# ONET8501P-breakout.net
KiCad netlist of a schematic drawn in EAGLE
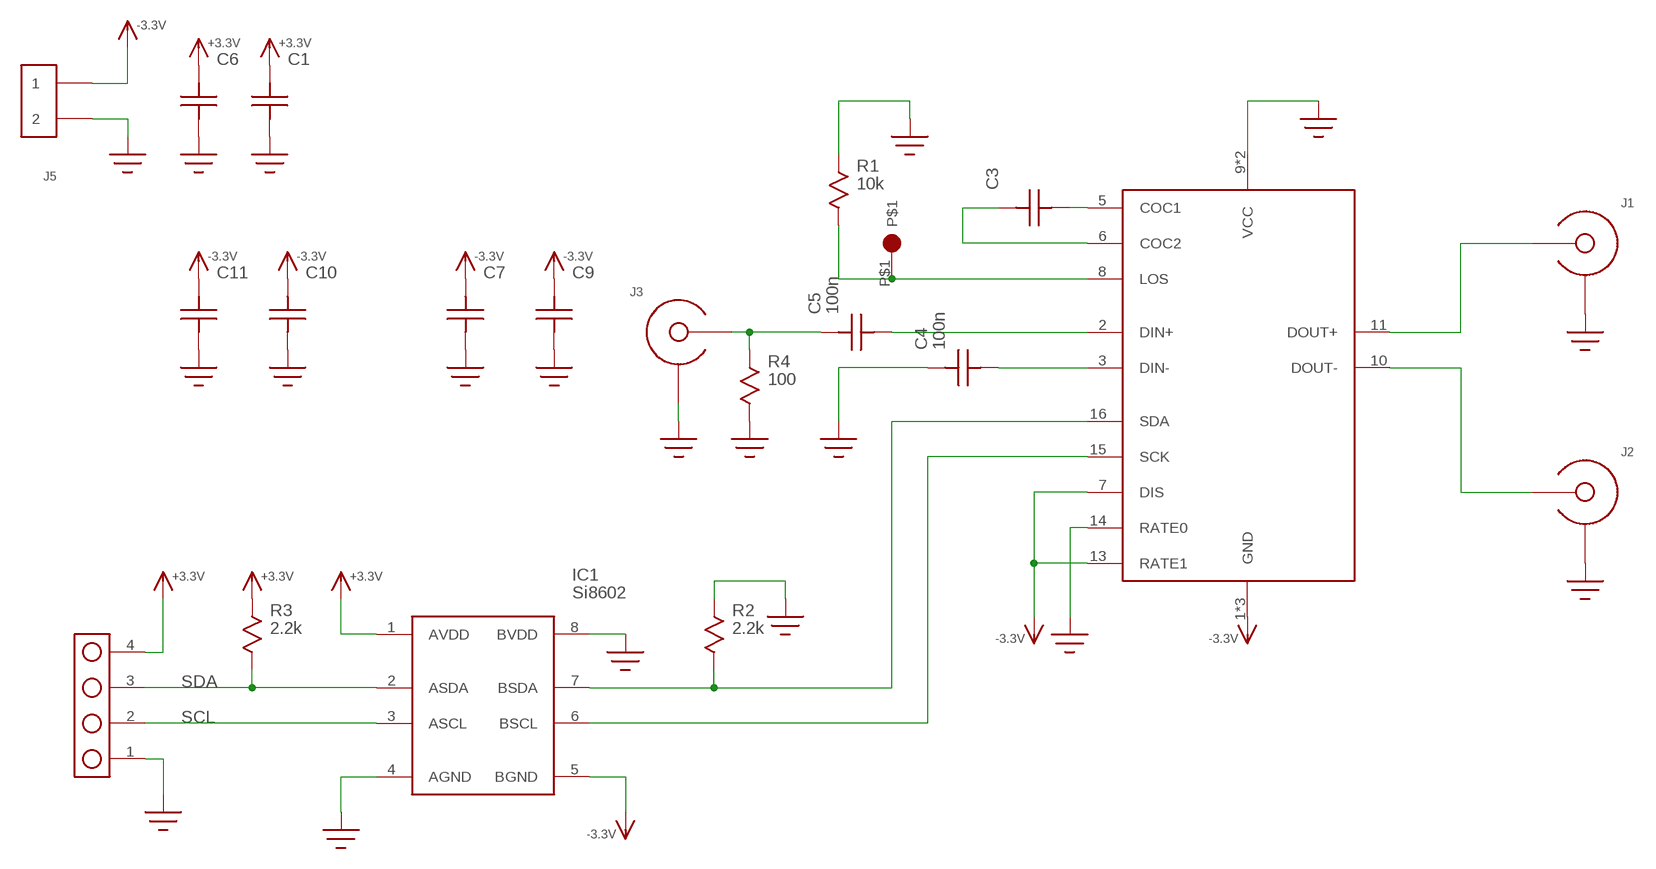
[diagram p0: schematic, sheet 1]

(export (version "E")
  (design (tool "Eeschema 10.0.6"))
  (components
    (comp (ref "C1")
      (value "C0603")
      (footprint "eagle-import:C0603")
      (libsource (lib "eagle-import") (part "C0603"))
    )
    (comp (ref "C3")
      (value "C0603")
      (footprint "eagle-import:C0603")
      (libsource (lib "eagle-import") (part "C0603"))
    )
    (comp (ref "C4")
      (value "100n")
      (footprint "eagle-import:C0603")
      (libsource (lib "eagle-import") (part "C0603"))
    )
    (comp (ref "C5")
      (value "100n")
      (footprint "eagle-import:C0603")
      (libsource (lib "eagle-import") (part "C0603"))
    )
    (comp (ref "C6")
      (value "C1206")
      (footprint "eagle-import:1206")
      (libsource (lib "eagle-import") (part "C1206"))
    )
    (comp (ref "C7")
      (value "C1206")
      (footprint "eagle-import:1206")
      (libsource (lib "eagle-import") (part "C1206"))
    )
    (comp (ref "C9")
      (value "C0603")
      (footprint "eagle-import:C0603")
      (libsource (lib "eagle-import") (part "C0603"))
    )
    (comp (ref "C10")
      (value "C0603")
      (footprint "eagle-import:C0603")
      (libsource (lib "eagle-import") (part "C0603"))
    )
    (comp (ref "C11")
      (value "C0603")
      (footprint "eagle-import:C0603")
      (libsource (lib "eagle-import") (part "C0603"))
    )
    (comp (ref "IC1")
      (value "Si8602")
      (footprint "eagle-import:SOIC8")
      (libsource (lib "eagle-import") (part "SI8602"))
    )
    (comp (ref "IC2")
      (value "ONET8501P")
      (footprint "eagle-import:TQFN16-EP")
      (libsource (lib "eagle-import") (part "ONET8501P"))
    )
    (comp (ref "J1")
      (value "SMA-EDGE-LAUNCH4L_4035_TAPER")
      (footprint "eagle-import:SMA_EDGE_LAUNCH_4L_4035_TAPER")
      (libsource (lib "eagle-import") (part "SMA-EDGE-LAUNCH4L_4035_TAPER"))
    )
    (comp (ref "J2")
      (value "SMA-EDGE-LAUNCH4L_4035_TAPER")
      (footprint "eagle-import:SMA_EDGE_LAUNCH_4L_4035_TAPER")
      (libsource (lib "eagle-import") (part "SMA-EDGE-LAUNCH4L_4035_TAPER"))
    )
    (comp (ref "J3")
      (value "SMA-EDGE-LAUNCH4L_4035_TAPER")
      (footprint "eagle-import:SMA_EDGE_LAUNCH_4L_4035_TAPER")
      (libsource (lib "eagle-import") (part "SMA-EDGE-LAUNCH4L_4035_TAPER"))
    )
    (comp (ref "J4")
      (value "HEADER_4PIN")
      (footprint "eagle-import:HEADER_4PIN")
      (libsource (lib "eagle-import") (part "HEADER_4PIN"))
    )
    (comp (ref "J5")
      (value "HEADER_2PIN")
      (footprint "eagle-import:HEADER_2PIN")
      (libsource (lib "eagle-import") (part "HEADER_2PIN"))
    )
    (comp (ref "P1")
      (value "ICSP_PAD")
      (footprint "eagle-import:ICSP_PAD")
      (libsource (lib "eagle-import") (part "ICSP_PAD"))
    )
    (comp (ref "R1")
      (value "10k")
      (footprint "eagle-import:R0603")
      (libsource (lib "eagle-import") (part "R0603"))
    )
    (comp (ref "R2")
      (value "2.2k")
      (footprint "eagle-import:R0603")
      (libsource (lib "eagle-import") (part "R0603"))
    )
    (comp (ref "R3")
      (value "2.2k")
      (footprint "eagle-import:R0603")
      (libsource (lib "eagle-import") (part "R0603"))
    )
    (comp (ref "R4")
      (value "100")
      (footprint "eagle-import:R0603")
      (libsource (lib "eagle-import") (part "R0603"))
    )
  )
  (nets
    (net (code "1") (name "+3.3V") (class "Default")
      (node (ref "C1") (pin "P$2") (pinfunction "P$2_P$2") (pintype "bidirectional"))
      (node (ref "C6") (pin "P$2") (pinfunction "P$2_P$2") (pintype "bidirectional"))
      (node (ref "IC1") (pin "1") (pinfunction "AVDD_1") (pintype "bidirectional"))
      (node (ref "J4") (pin "4") (pinfunction "4_4") (pintype "bidirectional"))
      (node (ref "R3") (pin "P$1") (pinfunction "P$3_P$1") (pintype "bidirectional"))
    )
    (net (code "2") (name "-3.3V") (class "Default")
      (node (ref "C10") (pin "P$2") (pinfunction "P$2_P$2") (pintype "bidirectional"))
      (node (ref "C11") (pin "P$2") (pinfunction "P$2_P$2") (pintype "bidirectional"))
      (node (ref "C7") (pin "P$2") (pinfunction "P$2_P$2") (pintype "bidirectional"))
      (node (ref "C9") (pin "P$2") (pinfunction "P$2_P$2") (pintype "bidirectional"))
      (node (ref "IC1") (pin "5") (pinfunction "BGND_5") (pintype "bidirectional"))
      (node (ref "IC2") (pin "1") (pinfunction "GND_1") (pintype "bidirectional"))
      (node (ref "IC2") (pin "13") (pinfunction "RATE1_13") (pintype "bidirectional"))
      (node (ref "IC2") (pin "4") (pinfunction "GND_4") (pintype "bidirectional"))
      (node (ref "IC2") (pin "7") (pinfunction "DIS_7") (pintype "bidirectional"))
      (node (ref "IC2") (pin "EP") (pinfunction "GND_EP") (pintype "bidirectional"))
      (node (ref "J5") (pin "1") (pinfunction "1_1") (pintype "bidirectional"))
    )
    (net (code "3") (name "/SCL") (class "Default")
      (node (ref "IC1") (pin "3") (pinfunction "ASCL_3") (pintype "bidirectional"))
      (node (ref "J4") (pin "2") (pinfunction "2_2") (pintype "bidirectional"))
    )
    (net (code "4") (name "/SDA") (class "Default")
      (node (ref "IC1") (pin "2") (pinfunction "ASDA_2") (pintype "bidirectional"))
      (node (ref "J4") (pin "3") (pinfunction "3_3") (pintype "bidirectional"))
      (node (ref "R3") (pin "P$2") (pinfunction "P$4_P$2") (pintype "bidirectional"))
    )
    (net (code "5") (name "GND") (class "Default")
      (node (ref "C1") (pin "P$1") (pinfunction "P$1_P$1") (pintype "bidirectional"))
      (node (ref "C10") (pin "P$1") (pinfunction "P$1_P$1") (pintype "bidirectional"))
      (node (ref "C11") (pin "P$1") (pinfunction "P$1_P$1") (pintype "bidirectional"))
      (node (ref "C4") (pin "P$2") (pinfunction "P$2_P$2") (pintype "bidirectional"))
      (node (ref "C6") (pin "P$1") (pinfunction "P$1_P$1") (pintype "bidirectional"))
      (node (ref "C7") (pin "P$1") (pinfunction "P$1_P$1") (pintype "bidirectional"))
      (node (ref "C9") (pin "P$1") (pinfunction "P$1_P$1") (pintype "bidirectional"))
      (node (ref "IC1") (pin "4") (pinfunction "AGND_4") (pintype "bidirectional"))
      (node (ref "IC1") (pin "8") (pinfunction "BVDD_8") (pintype "bidirectional"))
      (node (ref "IC2") (pin "12") (pinfunction "VCC_12") (pintype "bidirectional"))
      (node (ref "IC2") (pin "14") (pinfunction "RATE0_14") (pintype "bidirectional"))
      (node (ref "IC2") (pin "9") (pinfunction "VCC_9") (pintype "bidirectional"))
      (node (ref "J1") (pin "BOTTOM_GND") (pinfunction "SHIELD_BOTTOM_GND") (pintype "bidirectional"))
      (node (ref "J1") (pin "GND@1") (pinfunction "SHIELD_GND@1") (pintype "bidirectional"))
      (node (ref "J1") (pin "GND@14") (pinfunction "SHIELD_GND@14") (pintype "bidirectional"))
      (node (ref "J1") (pin "GND@15") (pinfunction "SHIELD_GND@15") (pintype "bidirectional"))
      (node (ref "J1") (pin "GND@16") (pinfunction "SHIELD_GND@16") (pintype "bidirectional"))
      (node (ref "J1") (pin "GND@17") (pinfunction "SHIELD_GND@17") (pintype "bidirectional"))
      (node (ref "J1") (pin "GND@2") (pinfunction "SHIELD_GND@2") (pintype "bidirectional"))
      (node (ref "J1") (pin "GND@3") (pinfunction "SHIELD_GND@3") (pintype "bidirectional"))
      (node (ref "J1") (pin "GND@4") (pinfunction "SHIELD_GND@4") (pintype "bidirectional"))
      (node (ref "J1") (pin "GND@5") (pinfunction "SHIELD_GND@5") (pintype "bidirectional"))
      (node (ref "J1") (pin "GND@6") (pinfunction "SHIELD_GND@6") (pintype "bidirectional"))
      (node (ref "J1") (pin "GND@7") (pinfunction "SHIELD_GND@7") (pintype "bidirectional"))
      (node (ref "J1") (pin "GND@8") (pinfunction "SHIELD_GND@8") (pintype "bidirectional"))
      (node (ref "J1") (pin "GND_PAD1") (pinfunction "SHIELD_GND_PAD1") (pintype "bidirectional"))
      (node (ref "J1") (pin "GND_PAD2") (pinfunction "SHIELD_GND_PAD2") (pintype "bidirectional"))
      (node (ref "J1") (pin "P$1") (pinfunction "SHIELD_P$1") (pintype "bidirectional"))
      (node (ref "J1") (pin "P$2") (pinfunction "SHIELD_P$2") (pintype "bidirectional"))
      (node (ref "J2") (pin "BOTTOM_GND") (pinfunction "SHIELD_BOTTOM_GND") (pintype "bidirectional"))
      (node (ref "J2") (pin "GND@1") (pinfunction "SHIELD_GND@1") (pintype "bidirectional"))
      (node (ref "J2") (pin "GND@14") (pinfunction "SHIELD_GND@14") (pintype "bidirectional"))
      (node (ref "J2") (pin "GND@15") (pinfunction "SHIELD_GND@15") (pintype "bidirectional"))
      (node (ref "J2") (pin "GND@16") (pinfunction "SHIELD_GND@16") (pintype "bidirectional"))
      (node (ref "J2") (pin "GND@17") (pinfunction "SHIELD_GND@17") (pintype "bidirectional"))
      (node (ref "J2") (pin "GND@2") (pinfunction "SHIELD_GND@2") (pintype "bidirectional"))
      (node (ref "J2") (pin "GND@3") (pinfunction "SHIELD_GND@3") (pintype "bidirectional"))
      (node (ref "J2") (pin "GND@4") (pinfunction "SHIELD_GND@4") (pintype "bidirectional"))
      (node (ref "J2") (pin "GND@5") (pinfunction "SHIELD_GND@5") (pintype "bidirectional"))
      (node (ref "J2") (pin "GND@6") (pinfunction "SHIELD_GND@6") (pintype "bidirectional"))
      (node (ref "J2") (pin "GND@7") (pinfunction "SHIELD_GND@7") (pintype "bidirectional"))
      (node (ref "J2") (pin "GND@8") (pinfunction "SHIELD_GND@8") (pintype "bidirectional"))
      (node (ref "J2") (pin "GND_PAD1") (pinfunction "SHIELD_GND_PAD1") (pintype "bidirectional"))
      (node (ref "J2") (pin "GND_PAD2") (pinfunction "SHIELD_GND_PAD2") (pintype "bidirectional"))
      (node (ref "J2") (pin "P$1") (pinfunction "SHIELD_P$1") (pintype "bidirectional"))
      (node (ref "J2") (pin "P$2") (pinfunction "SHIELD_P$2") (pintype "bidirectional"))
      (node (ref "J3") (pin "BOTTOM_GND") (pinfunction "SHIELD_BOTTOM_GND") (pintype "bidirectional"))
      (node (ref "J3") (pin "GND@1") (pinfunction "SHIELD_GND@1") (pintype "bidirectional"))
      (node (ref "J3") (pin "GND@14") (pinfunction "SHIELD_GND@14") (pintype "bidirectional"))
      (node (ref "J3") (pin "GND@15") (pinfunction "SHIELD_GND@15") (pintype "bidirectional"))
      (node (ref "J3") (pin "GND@16") (pinfunction "SHIELD_GND@16") (pintype "bidirectional"))
      (node (ref "J3") (pin "GND@17") (pinfunction "SHIELD_GND@17") (pintype "bidirectional"))
      (node (ref "J3") (pin "GND@2") (pinfunction "SHIELD_GND@2") (pintype "bidirectional"))
      (node (ref "J3") (pin "GND@3") (pinfunction "SHIELD_GND@3") (pintype "bidirectional"))
      (node (ref "J3") (pin "GND@4") (pinfunction "SHIELD_GND@4") (pintype "bidirectional"))
      (node (ref "J3") (pin "GND@5") (pinfunction "SHIELD_GND@5") (pintype "bidirectional"))
      (node (ref "J3") (pin "GND@6") (pinfunction "SHIELD_GND@6") (pintype "bidirectional"))
      (node (ref "J3") (pin "GND@7") (pinfunction "SHIELD_GND@7") (pintype "bidirectional"))
      (node (ref "J3") (pin "GND@8") (pinfunction "SHIELD_GND@8") (pintype "bidirectional"))
      (node (ref "J3") (pin "GND_PAD1") (pinfunction "SHIELD_GND_PAD1") (pintype "bidirectional"))
      (node (ref "J3") (pin "GND_PAD2") (pinfunction "SHIELD_GND_PAD2") (pintype "bidirectional"))
      (node (ref "J3") (pin "P$1") (pinfunction "SHIELD_P$1") (pintype "bidirectional"))
      (node (ref "J3") (pin "P$2") (pinfunction "SHIELD_P$2") (pintype "bidirectional"))
      (node (ref "J4") (pin "1") (pinfunction "1_1") (pintype "bidirectional"))
      (node (ref "J5") (pin "2") (pinfunction "2_2") (pintype "bidirectional"))
      (node (ref "R1") (pin "P$1") (pinfunction "P$3_P$1") (pintype "bidirectional"))
      (node (ref "R2") (pin "P$1") (pinfunction "P$3_P$1") (pintype "bidirectional"))
      (node (ref "R4") (pin "P$2") (pinfunction "P$4_P$2") (pintype "bidirectional"))
    )
    (net (code "6") (name "Net-(IC1-BSCL)") (class "Default")
      (node (ref "IC1") (pin "6") (pinfunction "BSCL_6") (pintype "bidirectional"))
      (node (ref "IC2") (pin "15") (pinfunction "SCK_15") (pintype "bidirectional"))
    )
    (net (code "7") (name "Net-(IC1-BSDA)") (class "Default")
      (node (ref "IC1") (pin "7") (pinfunction "BSDA_7") (pintype "bidirectional"))
      (node (ref "IC2") (pin "16") (pinfunction "SDA_16") (pintype "bidirectional"))
      (node (ref "R2") (pin "P$2") (pinfunction "P$4_P$2") (pintype "bidirectional"))
    )
    (net (code "8") (name "Net-(IC2-COC1)") (class "Default")
      (node (ref "C3") (pin "P$1") (pinfunction "P$1_P$1") (pintype "bidirectional"))
      (node (ref "IC2") (pin "5") (pinfunction "COC1_5") (pintype "bidirectional"))
    )
    (net (code "9") (name "Net-(IC2-COC2)") (class "Default")
      (node (ref "C3") (pin "P$2") (pinfunction "P$2_P$2") (pintype "bidirectional"))
      (node (ref "IC2") (pin "6") (pinfunction "COC2_6") (pintype "bidirectional"))
    )
    (net (code "10") (name "Net-(IC2-DIN+)") (class "Default")
      (node (ref "C5") (pin "P$1") (pinfunction "P$1_P$1") (pintype "bidirectional"))
      (node (ref "IC2") (pin "2") (pinfunction "DIN+_2") (pintype "bidirectional"))
    )
    (net (code "11") (name "Net-(IC2-DIN-)") (class "Default")
      (node (ref "C4") (pin "P$1") (pinfunction "P$1_P$1") (pintype "bidirectional"))
      (node (ref "IC2") (pin "3") (pinfunction "DIN-_3") (pintype "bidirectional"))
    )
    (net (code "12") (name "Net-(IC2-DOUT+)") (class "Default")
      (node (ref "IC2") (pin "11") (pinfunction "DOUT+_11") (pintype "bidirectional"))
      (node (ref "J1") (pin "CENTER@1") (pinfunction "CENTER_CENTER@1") (pintype "bidirectional"))
    )
    (net (code "13") (name "Net-(IC2-DOUT-)") (class "Default")
      (node (ref "IC2") (pin "10") (pinfunction "DOUT-_10") (pintype "bidirectional"))
      (node (ref "J2") (pin "CENTER@1") (pinfunction "CENTER_CENTER@1") (pintype "bidirectional"))
    )
    (net (code "14") (name "Net-(IC2-LOS)") (class "Default")
      (node (ref "IC2") (pin "8") (pinfunction "LOS_8") (pintype "bidirectional"))
      (node (ref "P1") (pin "P$1") (pinfunction "P$1_P$1") (pintype "bidirectional"))
      (node (ref "R1") (pin "P$2") (pinfunction "P$4_P$2") (pintype "bidirectional"))
    )
    (net (code "15") (name "Net-(J3-CENTER)") (class "Default")
      (node (ref "C5") (pin "P$2") (pinfunction "P$2_P$2") (pintype "bidirectional"))
      (node (ref "J3") (pin "CENTER@1") (pinfunction "CENTER_CENTER@1") (pintype "bidirectional"))
      (node (ref "R4") (pin "P$1") (pinfunction "P$3_P$1") (pintype "bidirectional"))
    )
  )
)
